# Sensors_PCB_v2_1.net
KiCad netlist of a schematic drawn in EAGLE
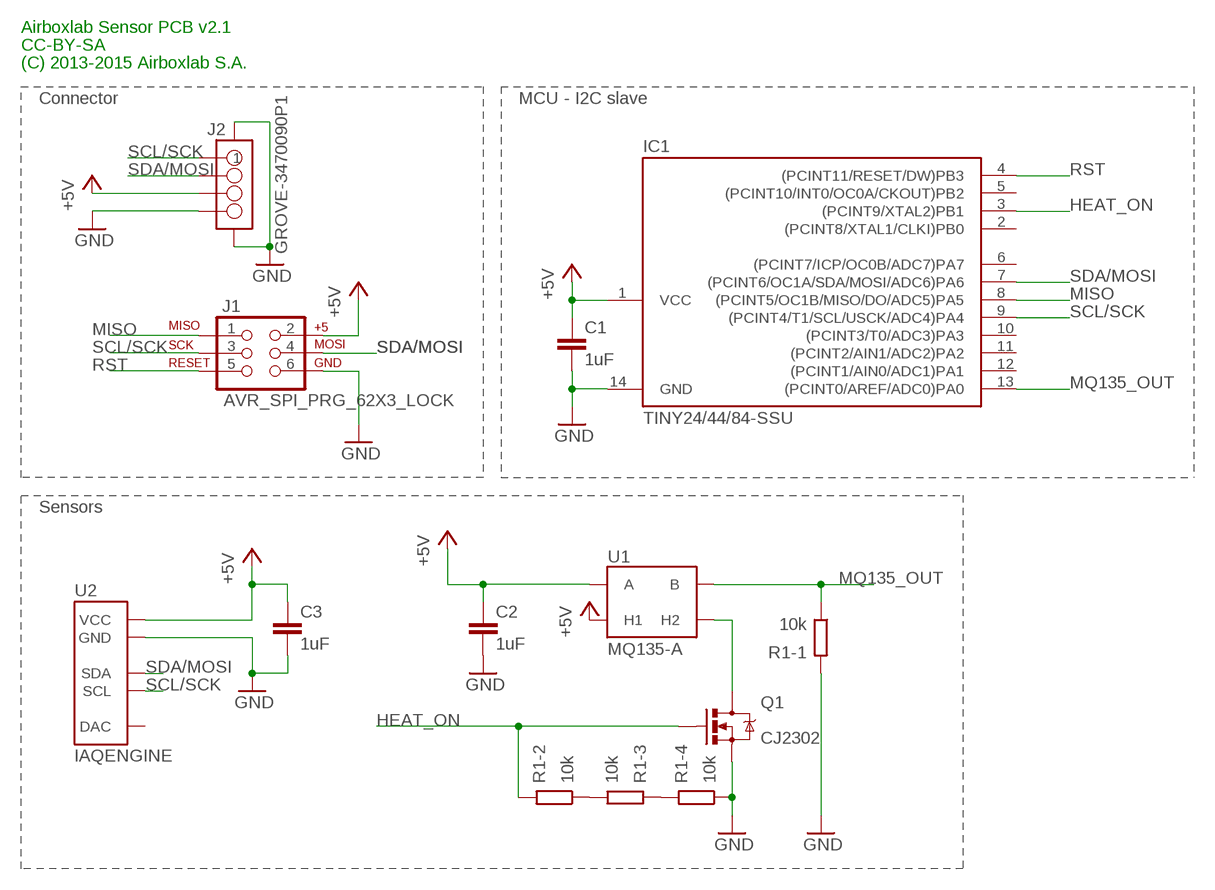
[diagram p0: schematic, sheet 1]

(export (version "E")
  (design (tool "Eeschema 10.0.6"))
  (components
    (comp (ref "C1")
      (value "1uF")
      (footprint "eagle-import:0603_N")
      (libsource (lib "eagle-import") (part "C0603"))
    )
    (comp (ref "C2")
      (value "1uF")
      (footprint "eagle-import:0603_N")
      (libsource (lib "eagle-import") (part "C0603"))
    )
    (comp (ref "C3")
      (value "1uF")
      (footprint "eagle-import:0603_N")
      (libsource (lib "eagle-import") (part "C0603"))
    )
    (comp (ref "IC1")
      (value "TINY24/44/84-SSU")
      (footprint "eagle-import:SOIC14")
      (libsource (lib "eagle-import") (part "TINY24/44/84-SSU"))
    )
    (comp (ref "J1")
      (value "AVR_SPI_PRG_62X3_LOCK")
      (footprint "eagle-import:2X3_LOCK")
      (libsource (lib "eagle-import") (part "AVR_SPI_PRG_62X3_LOCK"))
    )
    (comp (ref "J2")
      (value "GROVE-3470090P1")
      (footprint "eagle-import:4P-SMD-2.0")
      (libsource (lib "eagle-import") (part "GROVE-4P-2.0-SMD-FEMALE-REINFORCE-3470090P1"))
    )
    (comp (ref "Q1")
      (value "CJ2302")
      (footprint "eagle-import:SOT-23-3_N_SSOT-3_N")
      (libsource (lib "eagle-import") (part "MOSFET_N_SOT23-3"))
    )
    (comp (ref "R1")
      (value "10k")
      (footprint "eagle-import:R_0603_80P_4")
      (libsource (lib "eagle-import") (part "R_4"))
    )
    (comp (ref "U1")
      (value "MQ135-A")
      (footprint "eagle-import:MQ135-A")
      (libsource (lib "eagle-import") (part "MQ135-A"))
    )
    (comp (ref "U2")
      (value "IAQENGINE")
      (footprint "eagle-import:IAQENGINE")
      (libsource (lib "eagle-import") (part "IAQENGINE"))
    )
  )
  (nets
    (net (code "1") (name "+5V") (class "Default")
      (node (ref "C1") (pin "1") (pinfunction "1_1") (pintype "passive"))
      (node (ref "C2") (pin "1") (pinfunction "1_1") (pintype "passive"))
      (node (ref "C3") (pin "1") (pinfunction "1_1") (pintype "passive"))
      (node (ref "IC1") (pin "1") (pinfunction "VCC_1") (pintype "power_in"))
      (node (ref "J1") (pin "2") (pinfunction "2_2") (pintype "passive"))
      (node (ref "J2") (pin "3") (pinfunction "3_3") (pintype "bidirectional"))
      (node (ref "U1") (pin "1") (pinfunction "A_1") (pintype "bidirectional"))
      (node (ref "U1") (pin "2") (pinfunction "H1_2") (pintype "bidirectional"))
      (node (ref "U1") (pin "3") (pinfunction "A_3") (pintype "bidirectional"))
      (node (ref "U2") (pin "6") (pinfunction "VCC_6") (pintype "bidirectional"))
    )
    (net (code "2") (name "/HEAT_ON") (class "Default")
      (node (ref "IC1") (pin "3") (pinfunction "(PCINT9/XTAL2)PB1_3") (pintype "bidirectional"))
      (node (ref "Q1") (pin "1") (pinfunction "G_1") (pintype "passive"))
      (node (ref "R1") (pin "7") (pinfunction "2_7") (pintype "passive"))
    )
    (net (code "3") (name "/MISO") (class "Default")
      (node (ref "IC1") (pin "8") (pinfunction "(PCINT5/OC1B/MISO/DO/ADC5)PA5_8") (pintype "bidirectional"))
      (node (ref "J1") (pin "1") (pinfunction "1_1") (pintype "passive"))
    )
    (net (code "4") (name "/MQ135_OUT") (class "Default")
      (node (ref "IC1") (pin "13") (pinfunction "(PCINT0/AREF/ADC0)PA0_13") (pintype "bidirectional"))
      (node (ref "R1") (pin "1") (pinfunction "1_1") (pintype "passive"))
      (node (ref "U1") (pin "4") (pinfunction "B_4") (pintype "bidirectional"))
      (node (ref "U1") (pin "6") (pinfunction "B_6") (pintype "bidirectional"))
    )
    (net (code "5") (name "/RST") (class "Default")
      (node (ref "IC1") (pin "4") (pinfunction "(PCINT11/RESET/DW)PB3_4") (pintype "bidirectional"))
      (node (ref "J1") (pin "5") (pinfunction "5_5") (pintype "passive"))
    )
    (net (code "6") (name "/SCL{slash}SCK") (class "Default")
      (node (ref "IC1") (pin "9") (pinfunction "(PCINT4/T1/SCL/USCK/ADC4)PA4_9") (pintype "bidirectional"))
      (node (ref "J1") (pin "3") (pinfunction "3_3") (pintype "passive"))
      (node (ref "J2") (pin "1") (pinfunction "1_1") (pintype "bidirectional"))
      (node (ref "U2") (pin "2") (pinfunction "SCL_2") (pintype "bidirectional"))
    )
    (net (code "7") (name "/SDA{slash}MOSI") (class "Default")
      (node (ref "IC1") (pin "7") (pinfunction "(PCINT6/OC1A/SDA/MOSI/ADC6)PA6_7") (pintype "bidirectional"))
      (node (ref "J1") (pin "4") (pinfunction "4_4") (pintype "passive"))
      (node (ref "J2") (pin "2") (pinfunction "2_2") (pintype "bidirectional"))
      (node (ref "U2") (pin "4") (pinfunction "SDA_4") (pintype "bidirectional"))
    )
    (net (code "8") (name "GND") (class "Default")
      (node (ref "C1") (pin "2") (pinfunction "2_2") (pintype "passive"))
      (node (ref "C2") (pin "2") (pinfunction "2_2") (pintype "passive"))
      (node (ref "C3") (pin "2") (pinfunction "2_2") (pintype "passive"))
      (node (ref "IC1") (pin "14") (pinfunction "GND_14") (pintype "power_in"))
      (node (ref "J1") (pin "6") (pinfunction "6_6") (pintype "passive"))
      (node (ref "J2") (pin "4") (pinfunction "4_4") (pintype "bidirectional"))
      (node (ref "J2") (pin "SS1") (pinfunction "SS1_SS1") (pintype "bidirectional"))
      (node (ref "J2") (pin "SS2") (pinfunction "SS2_SS2") (pintype "bidirectional"))
      (node (ref "Q1") (pin "2") (pinfunction "S_2") (pintype "passive"))
      (node (ref "R1") (pin "4") (pinfunction "1_4") (pintype "passive"))
      (node (ref "R1") (pin "8") (pinfunction "2_8") (pintype "passive"))
      (node (ref "U2") (pin "3") (pinfunction "GND_3") (pintype "bidirectional"))
    )
    (net (code "9") (name "Net-(Q1-D)") (class "Default")
      (node (ref "Q1") (pin "3") (pinfunction "D_3") (pintype "passive"))
      (node (ref "U1") (pin "5") (pinfunction "H2_5") (pintype "bidirectional"))
    )
    (net (code "10") (name "Net-(R1B-1)") (class "Default")
      (node (ref "R1") (pin "2") (pinfunction "1_2") (pintype "passive"))
      (node (ref "R1") (pin "3") (pinfunction "1_3") (pintype "passive"))
    )
    (net (code "11") (name "Net-(R1C-2)") (class "Default")
      (node (ref "R1") (pin "5") (pinfunction "2_5") (pintype "passive"))
      (node (ref "R1") (pin "6") (pinfunction "2_6") (pintype "passive"))
    )
    (net (code "12") (name "unconnected-(IC1-(PCINT1{slash}AIN0{slash}ADC1)PA1-Pad12)") (class "Default")
      (node (ref "IC1") (pin "12") (pinfunction "(PCINT1/AIN0/ADC1)PA1_12") (pintype "bidirectional"))
    )
    (net (code "13") (name "unconnected-(IC1-(PCINT2{slash}AIN1{slash}ADC2)PA2-Pad11)") (class "Default")
      (node (ref "IC1") (pin "11") (pinfunction "(PCINT2/AIN1/ADC2)PA2_11") (pintype "bidirectional"))
    )
    (net (code "14") (name "unconnected-(IC1-(PCINT3{slash}T0{slash}ADC3)PA3-Pad10)") (class "Default")
      (node (ref "IC1") (pin "10") (pinfunction "(PCINT3/T0/ADC3)PA3_10") (pintype "bidirectional"))
    )
    (net (code "15") (name "unconnected-(IC1-(PCINT7{slash}ICP{slash}OC0B{slash}ADC7)PA7-Pad6)") (class "Default")
      (node (ref "IC1") (pin "6") (pinfunction "(PCINT7/ICP/OC0B/ADC7)PA7_6") (pintype "bidirectional"))
    )
    (net (code "16") (name "unconnected-(IC1-(PCINT8{slash}XTAL1{slash}CLKI)PB0-Pad2)") (class "Default")
      (node (ref "IC1") (pin "2") (pinfunction "(PCINT8/XTAL1/CLKI)PB0_2") (pintype "bidirectional"))
    )
    (net (code "17") (name "unconnected-(IC1-(PCINT10{slash}INT0{slash}OC0A{slash}CKOUT)PB2-Pad5)") (class "Default")
      (node (ref "IC1") (pin "5") (pinfunction "(PCINT10/INT0/OC0A/CKOUT)PB2_5") (pintype "bidirectional"))
    )
    (net (code "18") (name "unconnected-(U2-DAC-Pad1)") (class "Default")
      (node (ref "U2") (pin "1") (pinfunction "DAC_1") (pintype "bidirectional"))
    )
  )
)
